# delta.net
KiCad netlist of a schematic drawn in EasyEDA Pro
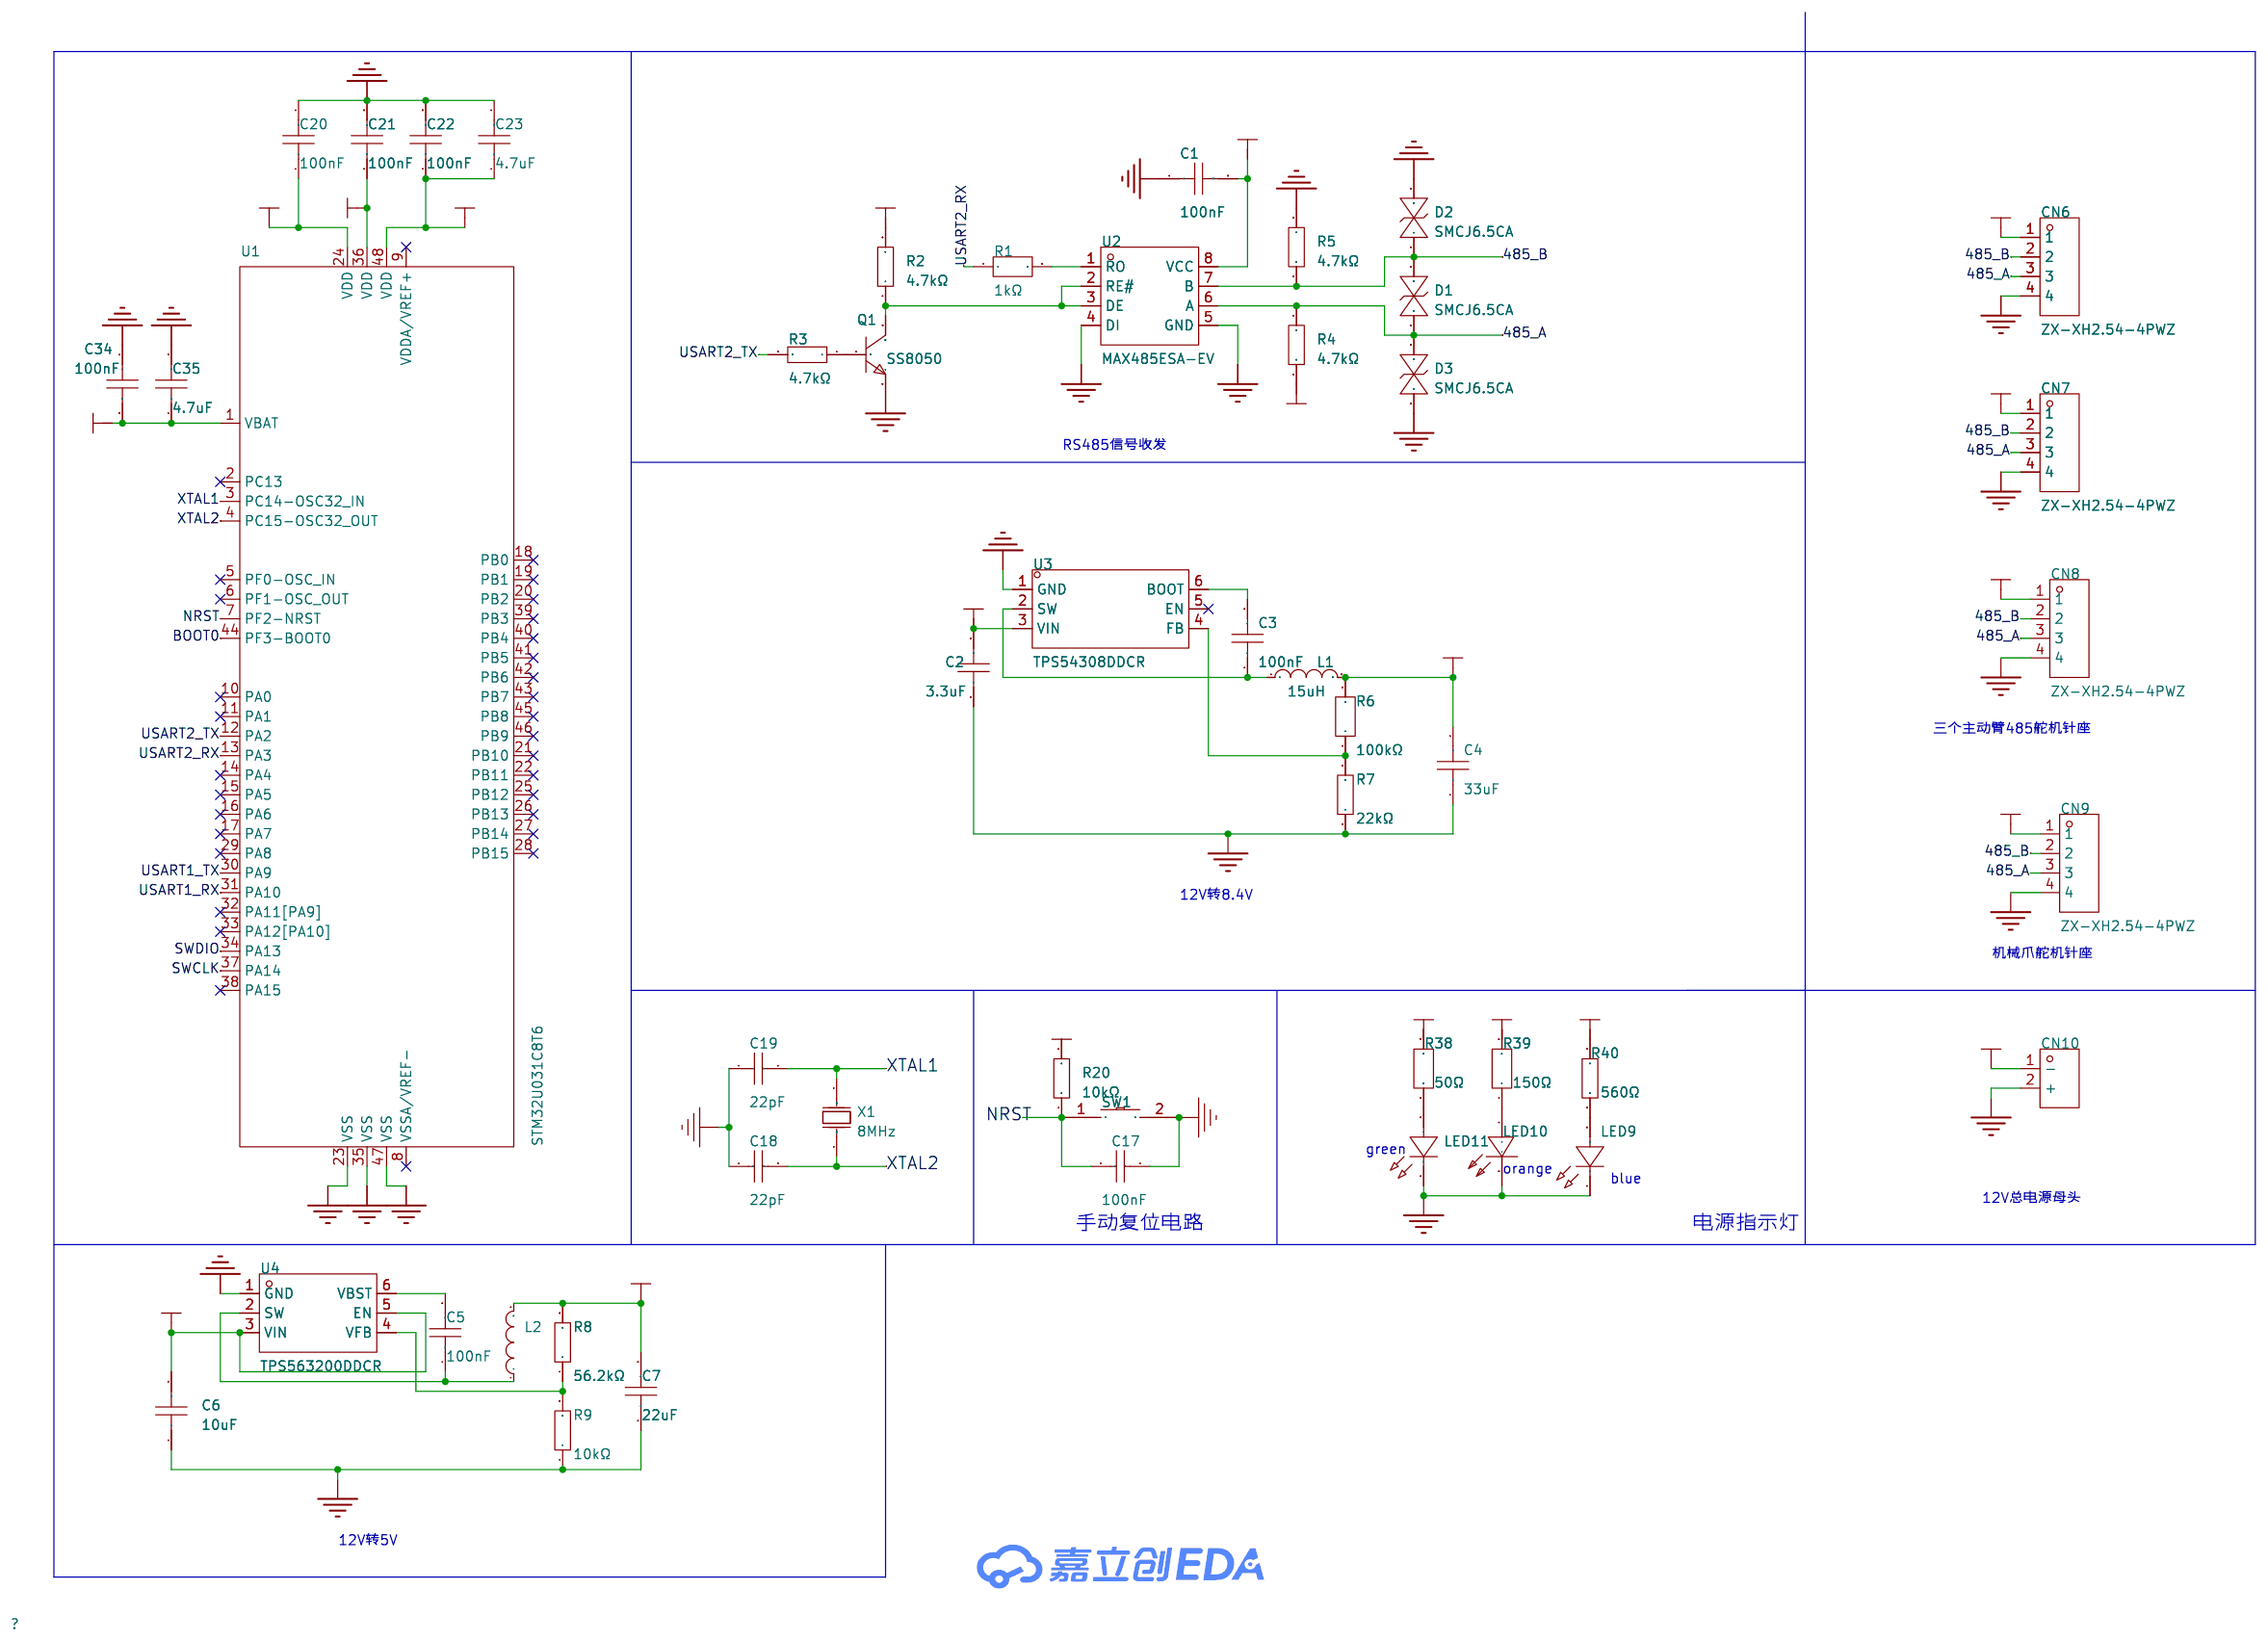
[diagram p0: P1]
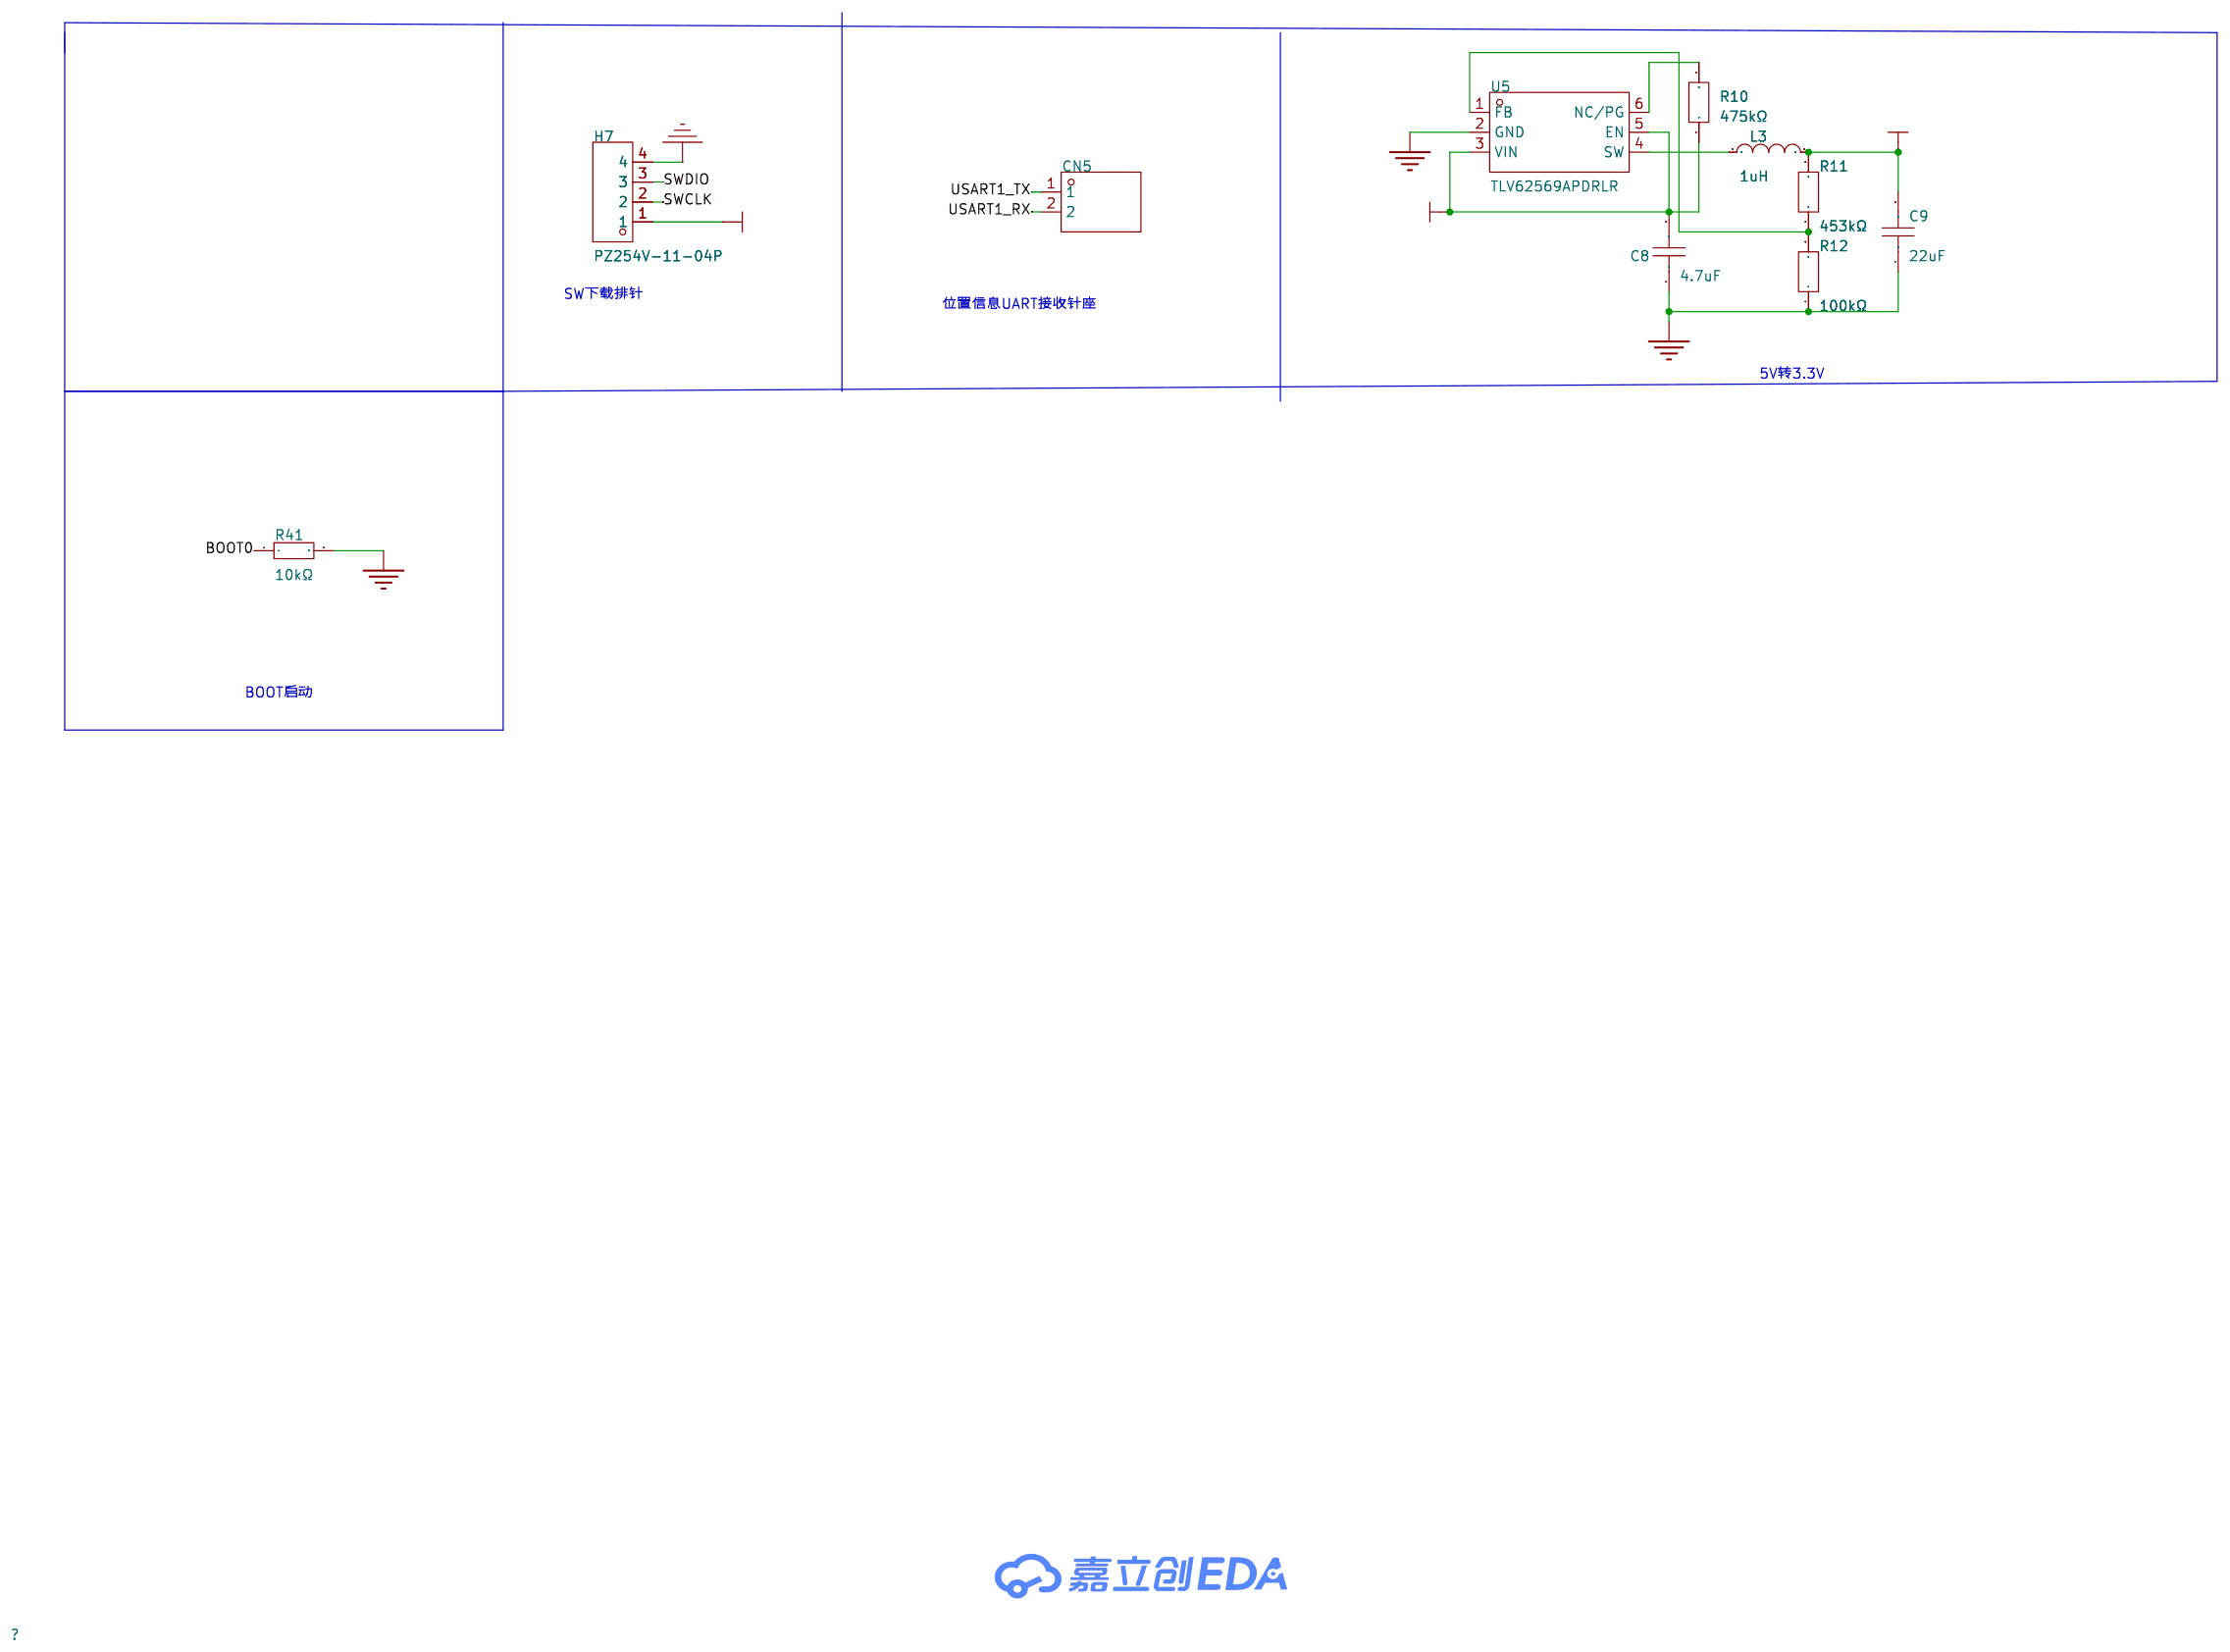
[diagram p1: P2]

(export (version "E")
  (design (tool "Eeschema 10.0.6"))
  (components
    (comp (ref "C1")
      (value "100nF")
      (footprint "easyedapro:C0603")
      (description "容值:100nF;精度:±10%;额定电压:50V;温度系数:X7R;")
      (fields
        (field (name "Manufacturer Part") "CGA0603X7R104K500JT")
        (field (name "Manufacturer") "HRE(芯声)")
      )
      (libsource (lib "easyedapro") (part "CGA0603X7R104K500JT"))
    )
    (comp (ref "C2")
      (value "3.3uF")
      (footprint "easyedapro:C0603")
      (description "容值:3.3uF;精度:±10%;额定电压:35V;温度系数:X5R;")
      (fields (field (name "Manufacturer Part") "C1608X5R1V335K080AC") (field (name "Manufacturer") "TDK"))
      (libsource (lib "easyedapro") (part "C1608X5R1V335K080AC"))
    )
    (comp (ref "C3")
      (value "100nF")
      (footprint "easyedapro:C0805")
      (description "容值:100nF;精度:±20%;额定电压:50V;材质(温度系数):X7R;")
      (fields (field (name "Manufacturer Part") "C0805C104M5RACTU") (field (name "Manufacturer") "KEMET(基美)"))
      (libsource (lib "easyedapro") (part "C0805C104M5RACTU"))
    )
    (comp (ref "C4")
      (value "33uF")
      (footprint "easyedapro:C0805")
      (description "容值:33uF;精度:±20%;额定电压:10V;温度系数:X5R;")
      (fields (field (name "Manufacturer Part") "C2012X5R1A336M125AC") (field (name "Manufacturer") "TDK"))
      (libsource (lib "easyedapro") (part "C2012X5R1A336M125AC"))
    )
    (comp (ref "C5")
      (value "100nF")
      (footprint "easyedapro:C0805")
      (description "容值:100nF;精度:±10%;额定电压:25V;材质(温度系数):X7R;")
      (fields (field (name "Manufacturer Part") "08053C104KAT2A") (field (name "Manufacturer") "Kyocera AVX"))
      (libsource (lib "easyedapro") (part "08053C104KAT2A"))
    )
    (comp (ref "C6")
      (value "10uF")
      (footprint "easyedapro:C0805")
      (description "容值:10uF;精度:±10%;额定电压:25V;材质(温度系数):X5R;")
      (fields
        (field (name "Manufacturer Part") "CL21A106KAYNNNE")
        (field (name "Manufacturer") "SAMSUNG(三星)")
      )
      (libsource (lib "easyedapro") (part "CL21A106KAYNNNE"))
    )
    (comp (ref "C7")
      (value "22uF")
      (footprint "easyedapro:C0805")
      (description "容值:22uF;精度:±20%;额定电压:10V;材质(温度系数):X5R;")
      (fields
        (field (name "Manufacturer Part") "GRM21BR61A226ME44L")
        (field (name "Manufacturer") "muRata(村田)")
      )
      (libsource (lib "easyedapro") (part "GRM21BR61A226ME44L"))
    )
    (comp (ref "C17")
      (value "100nF")
      (footprint "easyedapro:C0805")
      (description "容值:100nF;精度:±10%;额定电压:100V;材质(温度系数):X7R;")
      (fields
        (field (name "Manufacturer Part") "CL21B104KCFNNNE")
        (field (name "Manufacturer") "SAMSUNG(三星)")
      )
      (libsource (lib "easyedapro") (part "CL21B104KCFNNNE"))
    )
    (comp (ref "C18")
      (value "22pF")
      (footprint "easyedapro:C0805")
      (description "容值:22pF;精度:±5%;额定电压:50V;材质(温度系数):C0G;")
      (fields
        (field (name "Manufacturer Part") "CL21C220JBANNNC")
        (field (name "Manufacturer") "SAMSUNG(三星)")
      )
      (libsource (lib "easyedapro") (part "CL21C220JBANNNC"))
    )
    (comp (ref "C19")
      (value "22pF")
      (footprint "easyedapro:C0805")
      (description "容值:22pF;精度:±5%;额定电压:50V;材质(温度系数):C0G;")
      (fields
        (field (name "Manufacturer Part") "CL21C220JBANNNC")
        (field (name "Manufacturer") "SAMSUNG(三星)")
      )
      (libsource (lib "easyedapro") (part "CL21C220JBANNNC"))
    )
    (comp (ref "C20")
      (value "100nF")
      (footprint "easyedapro:C0805")
      (description "容值:100nF;精度:±10%;额定电压:50V;材质(温度系数):X7R;")
      (fields
        (field (name "Manufacturer Part") "CC0805KRX7R9BB104")
        (field (name "Manufacturer") "YAGEO(国巨)")
      )
      (libsource (lib "easyedapro") (part "CC0805KRX7R9BB104"))
    )
    (comp (ref "C21")
      (value "100nF")
      (footprint "easyedapro:C0805")
      (description "容值:100nF;精度:±10%;额定电压:50V;材质(温度系数):X7R;")
      (fields
        (field (name "Manufacturer Part") "CC0805KRX7R9BB104")
        (field (name "Manufacturer") "YAGEO(国巨)")
      )
      (libsource (lib "easyedapro") (part "CC0805KRX7R9BB104"))
    )
    (comp (ref "C22")
      (value "100nF")
      (footprint "easyedapro:C0805")
      (description "容值:100nF;精度:±10%;额定电压:50V;材质(温度系数):X7R;")
      (fields
        (field (name "Manufacturer Part") "CC0805KRX7R9BB104")
        (field (name "Manufacturer") "YAGEO(国巨)")
      )
      (libsource (lib "easyedapro") (part "CC0805KRX7R9BB104"))
    )
    (comp (ref "C23")
      (value "4.7uF")
      (footprint "easyedapro:C0805")
      (description "容值:4.7uF;精度:±10%;额定电压:35V;材质(温度系数):X7R;")
      (fields
        (field (name "Manufacturer Part") "CGA0805X7R475K350MT")
        (field (name "Manufacturer") "HRE(芯声)")
      )
      (libsource (lib "easyedapro") (part "CGA0805X7R475K350MT"))
    )
    (comp (ref "C34")
      (value "100nF")
      (footprint "easyedapro:C0805")
      (description "容值:100nF;精度:±10%;额定电压:50V;材质(温度系数):X7R;")
      (fields
        (field (name "Manufacturer Part") "CC0805KRX7R9BB104")
        (field (name "Manufacturer") "YAGEO(国巨)")
      )
      (libsource (lib "easyedapro") (part "CC0805KRX7R9BB104"))
    )
    (comp (ref "C35")
      (value "4.7uF")
      (footprint "easyedapro:C0805")
      (description "容值:4.7uF;精度:±10%;额定电压:35V;材质(温度系数):X7R;")
      (fields
        (field (name "Manufacturer Part") "CGA0805X7R475K350MT")
        (field (name "Manufacturer") "HRE(芯声)")
      )
      (libsource (lib "easyedapro") (part "CGA0805X7R475K350MT"))
    )
    (comp (ref "CN6")
      (value "ZX-XH2.54-4PWZ")
      (footprint "easyedapro:CONN-TH_4P-P2.50_ZX-XH2.54-4PWZ")
      (fields (field (name "Manufacturer") "Megastar(兆星)"))
      (libsource (lib "easyedapro") (part "ZX-XH2.54-4PWZ"))
    )
    (comp (ref "CN7")
      (value "ZX-XH2.54-4PWZ")
      (footprint "easyedapro:CONN-TH_4P-P2.50_ZX-XH2.54-4PWZ")
      (fields (field (name "Manufacturer") "Megastar(兆星)"))
      (libsource (lib "easyedapro") (part "ZX-XH2.54-4PWZ"))
    )
    (comp (ref "CN8")
      (value "ZX-XH2.54-4PWZ")
      (footprint "easyedapro:CONN-TH_4P-P2.50_ZX-XH2.54-4PWZ")
      (fields (field (name "Manufacturer") "Megastar(兆星)"))
      (libsource (lib "easyedapro") (part "ZX-XH2.54-4PWZ"))
    )
    (comp (ref "CN9")
      (value "ZX-XH2.54-4PWZ")
      (footprint "easyedapro:CONN-TH_4P-P2.50_ZX-XH2.54-4PWZ")
      (fields (field (name "Manufacturer") "Megastar(兆星)"))
      (libsource (lib "easyedapro") (part "ZX-XH2.54-4PWZ"))
    )
    (comp (ref "CN10")
      (value "XT30UPB-M")
      (footprint "easyedapro:CONN-TH_XT30UPB-M")
      (description "类别:-;类型1:-;")
      (fields (field (name "Manufacturer") "AMASS(艾迈斯)"))
      (libsource (lib "easyedapro") (part "XT30UPB-M"))
    )
    (comp (ref "D1")
      (value "SMCJ6.5CA")
      (footprint "easyedapro:SMC_L6.8-W5.9-LS7.9-BI")
      (fields (field (name "Manufacturer") "Brightking(君耀电子)"))
      (libsource (lib "easyedapro") (part "SMCJ6.5CA_C20623833"))
    )
    (comp (ref "D2")
      (value "SMCJ6.5CA")
      (footprint "easyedapro:SMC_L6.8-W5.9-LS7.9-BI")
      (fields (field (name "Manufacturer") "Brightking(君耀电子)"))
      (libsource (lib "easyedapro") (part "SMCJ6.5CA_C20623833"))
    )
    (comp (ref "D3")
      (value "SMCJ6.5CA")
      (footprint "easyedapro:SMC_L6.8-W5.9-LS7.9-BI")
      (fields (field (name "Manufacturer") "Brightking(君耀电子)"))
      (libsource (lib "easyedapro") (part "SMCJ6.5CA_C20623833"))
    )
    (comp (ref "L1")
      (value "15uH")
      (footprint "easyedapro:IND-SMD_L10.2-W10.0")
      (description "电感值:15uH;精度:±20%;")
      (fields
        (field (name "Manufacturer Part") "MSS1038-153MLC")
        (field (name "Manufacturer") "Coilcraft(线艺)")
      )
      (libsource (lib "easyedapro") (part "MSS1038-153MLC"))
    )
    (comp (ref "L2")
      (value "VLP8040T-3R3N")
      (footprint "easyedapro:IND-SMD_L8.7-W8.6")
      (description "精度:±30%;")
      (fields (field (name "Manufacturer") "TDK"))
      (libsource (lib "easyedapro") (part "VLP8040T-3R3N"))
    )
    (comp (ref "LED9")
      (value "XL-1608UBC-04")
      (footprint "easyedapro:LED0603-RD_BLUE")
      (fields (field (name "Manufacturer") "XINGLIGHT(成兴光)"))
      (libsource (lib "easyedapro") (part "XL-1608UBC-04"))
    )
    (comp (ref "LED10")
      (value "SZYY0603O")
      (footprint "easyedapro:LED0603-R-RD_ORANGE")
      (fields (field (name "Manufacturer") "yongyu(永裕光电)"))
      (libsource (lib "easyedapro") (part "SZYY0603O"))
    )
    (comp (ref "LED11")
      (value "TZ-P2-0603YGTCS1-0.6T")
      (footprint "easyedapro:LED0603-RD")
      (fields (field (name "Manufacturer") "TUOZHAN(拓展光电)"))
      (libsource (lib "easyedapro") (part "TZ-P2-0603YGTCS1-0.6T"))
    )
    (comp (ref "Q1")
      (value "SS8050")
      (footprint "easyedapro:SOT-23-3_L2.9-W1.3-P1.90-LS2.4-BR")
      (fields (field (name "Manufacturer") "Doeshare(德芯)"))
      (libsource (lib "easyedapro") (part "SS8050_C2931717"))
    )
    (comp (ref "R1")
      (value "1kΩ")
      (footprint "easyedapro:R0603")
      (description "电阻类型:厚膜电阻;阻值:1kΩ;精度:±1%;功率:100mW;最大工作电压:75V;")
      (fields (field (name "Manufacturer Part") "FCR0603F1K") (field (name "Manufacturer") "VO(翔胜)"))
      (libsource (lib "easyedapro") (part "FCR0603F1K"))
    )
    (comp (ref "R2")
      (value "4.7kΩ")
      (footprint "easyedapro:R0603")
      (description "电阻类型:厚膜电阻;阻值:4.7kΩ;精度:±1%;功率:100mW;最大工作电压:75V;温度系数:±100ppm/°C;")
      (fields
        (field (name "Manufacturer Part") "0603WAF4701T5E")
        (field (name "Manufacturer") "UNI-ROYAL(厚声)")
      )
      (libsource (lib "easyedapro") (part "0603WAF4701T5E"))
    )
    (comp (ref "R3")
      (value "4.7kΩ")
      (footprint "easyedapro:R0603")
      (description "电阻类型:厚膜电阻;阻值:4.7kΩ;精度:±1%;功率:100mW;最大工作电压:75V;温度系数:±100ppm/°C;")
      (fields
        (field (name "Manufacturer Part") "0603WAF4701T5E")
        (field (name "Manufacturer") "UNI-ROYAL(厚声)")
      )
      (libsource (lib "easyedapro") (part "0603WAF4701T5E"))
    )
    (comp (ref "R4")
      (value "4.7kΩ")
      (footprint "easyedapro:R0603")
      (description "电阻类型:厚膜电阻;阻值:4.7kΩ;精度:±1%;功率:100mW;最大工作电压:75V;温度系数:±100ppm/°C;")
      (fields
        (field (name "Manufacturer Part") "0603WAF4701T5E")
        (field (name "Manufacturer") "UNI-ROYAL(厚声)")
      )
      (libsource (lib "easyedapro") (part "0603WAF4701T5E"))
    )
    (comp (ref "R5")
      (value "4.7kΩ")
      (footprint "easyedapro:R0603")
      (description "电阻类型:厚膜电阻;阻值:4.7kΩ;精度:±1%;功率:100mW;最大工作电压:75V;温度系数:±100ppm/°C;")
      (fields
        (field (name "Manufacturer Part") "0603WAF4701T5E")
        (field (name "Manufacturer") "UNI-ROYAL(厚声)")
      )
      (libsource (lib "easyedapro") (part "0603WAF4701T5E"))
    )
    (comp (ref "R6")
      (value "100kΩ")
      (footprint "easyedapro:R0402")
      (description "电阻类型:厚膜电阻;阻值:100kΩ;精度:±1%;功率:63mW;工作电压:75V;温度系数:±100ppm/°C;")
      (fields
        (field (name "Manufacturer Part") "CRCW0402100KFKED")
        (field (name "Manufacturer") "VISHAY(威世)")
      )
      (libsource (lib "easyedapro") (part "CRCW0402100KFKED"))
    )
    (comp (ref "R7")
      (value "22kΩ")
      (footprint "easyedapro:R0603")
      (description "电阻类型:厚膜电阻;阻值:22kΩ;精度:±1%;功率:100mW;工作电压:75V;温度系数:±100ppm/°C;")
      (fields (field (name "Manufacturer Part") "RC0603FR-0722KL") (field (name "Manufacturer") "YAGEO(国巨)"))
      (libsource (lib "easyedapro") (part "RC0603FR-0722KL"))
    )
    (comp (ref "R8")
      (value "56.2kΩ")
      (footprint "easyedapro:R0201")
      (description "电阻类型:厚膜电阻;阻值:56.2kΩ;精度:±1%;功率:50mW;工作电压:25V;温度系数:±200ppm/°C;")
      (fields (field (name "Manufacturer Part") "RC0201FR-0756K2L") (field (name "Manufacturer") "YAGEO(国巨)"))
      (libsource (lib "easyedapro") (part "RC0201FR-0756K2L"))
    )
    (comp (ref "R9")
      (value "10kΩ")
      (footprint "easyedapro:R0201")
      (description "电阻类型:厚膜电阻;阻值:10kΩ;精度:±1%;功率:50mW;工作电压:25V;温度系数:±200ppm/°C;")
      (fields (field (name "Manufacturer Part") "RC0201FR-0710KL") (field (name "Manufacturer") "YAGEO(国巨)"))
      (libsource (lib "easyedapro") (part "RC0201FR-0710KL"))
    )
    (comp (ref "R20")
      (value "10kΩ")
      (footprint "easyedapro:R0805")
      (description "电阻类型:厚膜电阻;阻值:10kΩ;精度:±1%;功率:125mW;最大工作电压:150V;温度系数:±100ppm/°C;")
      (fields
        (field (name "Manufacturer Part") "0805W8F1002T5E")
        (field (name "Manufacturer") "UNI-ROYAL(厚声)")
      )
      (libsource (lib "easyedapro") (part "0805W8F1002T5E"))
    )
    (comp (ref "R38")
      (value "50Ω")
      (footprint "easyedapro:R0805")
      (description "电阻类型:薄膜电阻;阻值:50Ω;精度:±1%;功率:125mW;最大工作电压:150V;温度系数:±25ppm/°C;")
      (fields (field (name "Manufacturer Part") "ARG05FTC0500") (field (name "Manufacturer") "Viking(光颉)"))
      (libsource (lib "easyedapro") (part "ARG05FTC0500"))
    )
    (comp (ref "R39")
      (value "150Ω")
      (footprint "easyedapro:R0805")
      (description "电阻类型:厚膜电阻;阻值:150Ω;精度:±5%;功率:125mW;最大工作电压:150V;温度系数:±100ppm/°C;")
      (fields (field (name "Manufacturer Part") "FRC0805J151 TS") (field (name "Manufacturer") "FOJAN(富捷)"))
      (libsource (lib "easyedapro") (part "FRC0805J151 TS"))
    )
    (comp (ref "R40")
      (value "560Ω")
      (footprint "easyedapro:R0805")
      (description "电阻类型:厚膜电阻;阻值:560Ω;精度:±1%;功率:125mW;最大工作电压:150V;温度系数:±100ppm/°C;")
      (fields
        (field (name "Manufacturer Part") "0805W8F5600T5E")
        (field (name "Manufacturer") "UNI-ROYAL(厚声)")
      )
      (libsource (lib "easyedapro") (part "0805W8F5600T5E"))
    )
    (comp (ref "SW1")
      (value "TS-1101-C-W")
      (footprint "easyedapro:SW-SMD_L6.0-W3.3-LS8.0")
      (fields (field (name "Manufacturer") "XKB Connectivity(中国星坤)"))
      (libsource (lib "easyedapro") (part "TS-1101-C-W"))
    )
    (comp (ref "U1")
      (value "STM32U031C8T6")
      (footprint "easyedapro:LQFP-48_L7.0-W7.0-P0.50-LS9.0-BL_1")
      (libsource (lib "easyedapro") (part "STM32U031C8T6"))
    )
    (comp (ref "U2")
      (value "MAX485ESA-EV")
      (footprint "easyedapro:SOIC-8_L4.9-W3.9-P1.27-LS6.0-BL")
      (description "低功耗、限摆率、RS-485/RS-422收发器")
      (fields (field (name "Manufacturer") "EVVO(翊欧)"))
      (libsource (lib "easyedapro") (part "MAX485ESA-EV"))
    )
    (comp (ref "U3")
      (value "TPS54308DDCR")
      (footprint "easyedapro:SOT-23-6_L2.9-W1.6-P0.95-LS2.8-BR")
      (description "功能类型:降压型;输出类型:固定;工作电压:4.5V~28V;输出电压:3.3V;输出电流:3A;")
      (fields (field (name "Manufacturer") "TI(德州仪器)"))
      (libsource (lib "easyedapro") (part "TPS54308DDCR"))
    )
    (comp (ref "U4")
      (value "TPS563200DDCR")
      (footprint "easyedapro:SOT-23-6_L2.9-W1.6-P0.95-LS2.8-BR")
      (description "功能类型:降压型;输出类型:可调;工作电压:4.5V~17V;输出电压:760mV~7V;输出电流:3A;")
      (fields (field (name "Manufacturer") "TI(德州仪器)"))
      (libsource (lib "easyedapro") (part "TPS563200DDCR"))
    )
    (comp (ref "X1")
      (value "8MHz")
      (footprint "easyedapro:CRYSTAL-SMD_L11.5-W4.8-LS12.7")
      (description "晶振类型:贴片晶振;频率:8MHz;常温频差:±20ppm;负载电容:20pF;频率稳定度:±30ppm;")
      (fields (field (name "Manufacturer Part") "X49SM8MSD2SC") (field (name "Manufacturer") "YXC(扬兴晶振)"))
      (libsource (lib "easyedapro") (part "X49SM8MSD2SC"))
    )
    (comp (ref "C8")
      (value "4.7uF")
      (footprint "easyedapro:C0603")
      (description "容值:4.7uF;精度:±10%;额定电压:16V;温度系数:X5R;")
      (fields
        (field (name "Manufacturer Part") "CL10A475KO8NNNC")
        (field (name "Manufacturer") "SAMSUNG(三星)")
      )
      (libsource (lib "easyedapro") (part "CL10A475KO8NNNC"))
    )
    (comp (ref "C9")
      (value "22uF")
      (footprint "easyedapro:C0603")
      (description "容值:22uF;精度:±20%;额定电压:6.3V;材质(温度系数):X5R;")
      (fields
        (field (name "Manufacturer Part") "GRM188R60J226MEA0D")
        (field (name "Manufacturer") "muRata(村田)")
      )
      (libsource (lib "easyedapro") (part "GRM188R60J226MEA0D"))
    )
    (comp (ref "CN5")
      (value "B2B-XH-A(LF)(SN)")
      (footprint "easyedapro:CONN-TH_B2B-XH-A-LF-SN")
      (fields (field (name "Manufacturer") "JST"))
      (libsource (lib "easyedapro") (part "B2B-XH-A (LF)(SN)"))
    )
    (comp (ref "H7")
      (value "PZ254V-11-04P")
      (footprint "easyedapro:HDR-TH_4P-P2.54-V-M")
      (fields (field (name "Manufacturer") "XFCN(兴飞)"))
      (libsource (lib "easyedapro") (part "PZ254V-11-04P_C2691448"))
    )
    (comp (ref "L3")
      (value "1uH")
      (footprint "easyedapro:IND-SMD_L8.2-W7.9")
      (description "电感值:1uH;精度:±30%;额定电流:7.8A;饱和电流(Isat):11A;类型:-;")
      (fields (field (name "Manufacturer Part") "SRN8040-1R0Y") (field (name "Manufacturer") "BOURNS"))
      (libsource (lib "easyedapro") (part "SRN8040-1R0Y"))
    )
    (comp (ref "R10")
      (value "475kΩ")
      (footprint "easyedapro:R0402")
      (description "电阻类型:厚膜电阻;阻值:475kΩ;精度:±1%;功率:62.5mW;最大工作电压:75V;温度系数:±100ppm/°C;")
      (fields
        (field (name "Manufacturer Part") "CRCW0402475KFKED")
        (field (name "Manufacturer") "VISHAY(威世)")
      )
      (libsource (lib "easyedapro") (part "CRCW0402475KFKED"))
    )
    (comp (ref "R11")
      (value "453kΩ")
      (footprint "easyedapro:R0402")
      (description "电阻类型:厚膜电阻;阻值:453kΩ;精度:±1%;功率:62.5mW;工作电压:50V;温度系数:±100ppm/°C;")
      (fields
        (field (name "Manufacturer Part") "CRCW0402453KFKED")
        (field (name "Manufacturer") "VISHAY(威世)")
      )
      (libsource (lib "easyedapro") (part "CRCW0402453KFKED"))
    )
    (comp (ref "R12")
      (value "100kΩ")
      (footprint "easyedapro:R0402")
      (description "电阻类型:厚膜电阻;阻值:100kΩ;精度:±1%;功率:63mW;工作电压:75V;温度系数:±100ppm/°C;")
      (fields
        (field (name "Manufacturer Part") "CRCW0402100KFKED")
        (field (name "Manufacturer") "VISHAY(威世)")
      )
      (libsource (lib "easyedapro") (part "CRCW0402100KFKED"))
    )
    (comp (ref "R41")
      (value "10kΩ")
      (footprint "easyedapro:R0805")
      (description "电阻类型:厚膜电阻;阻值:10kΩ;精度:±1%;功率:125mW;最大工作电压:150V;温度系数:±100ppm/°C;")
      (fields
        (field (name "Manufacturer Part") "0805W8F1002T5E")
        (field (name "Manufacturer") "UNI-ROYAL(厚声)")
      )
      (libsource (lib "easyedapro") (part "0805W8F1002T5E"))
    )
    (comp (ref "U5")
      (value "TLV62569APDRLR")
      (footprint "easyedapro:SOT-563_L1.6-W1.2-P0.50-LS1.6-BR")
      (description "功能类型:降压型;输出类型:可调;工作电压:2.5V~5.5V;输出电压:600mV~5.5V;输出电流:2A;")
      (fields (field (name "Manufacturer") "TI(德州仪器)"))
      (libsource (lib "easyedapro") (part "TLV62569APDRLR"))
    )
  )
  (nets
    (net (code "1") (name "3.3V") (class "Default")
      (node (ref "C1") (pin "2") (pinfunction "2_2") (pintype "unspecified"))
      (node (ref "C20") (pin "1") (pinfunction "1_1") (pintype "unspecified"))
      (node (ref "C21") (pin "1") (pinfunction "1_1") (pintype "unspecified"))
      (node (ref "C22") (pin "1") (pinfunction "1_1") (pintype "unspecified"))
      (node (ref "C23") (pin "1") (pinfunction "1_1") (pintype "unspecified"))
      (node (ref "C34") (pin "2") (pinfunction "2_2") (pintype "unspecified"))
      (node (ref "C35") (pin "1") (pinfunction "1_1") (pintype "unspecified"))
      (node (ref "C9") (pin "2") (pinfunction "2_2") (pintype "unspecified"))
      (node (ref "H7") (pin "1") (pinfunction "1_1") (pintype "unspecified"))
      (node (ref "L3") (pin "2") (pinfunction "2_2") (pintype "unspecified"))
      (node (ref "R11") (pin "2") (pinfunction "2_2") (pintype "unspecified"))
      (node (ref "R2") (pin "2") (pinfunction "2_2") (pintype "input"))
      (node (ref "R20") (pin "2") (pinfunction "2_2") (pintype "input"))
      (node (ref "R38") (pin "2") (pinfunction "2_2") (pintype "unspecified"))
      (node (ref "R4") (pin "2") (pinfunction "2_2") (pintype "input"))
      (node (ref "U1") (pin "1") (pinfunction "VBAT_1") (pintype "unspecified"))
      (node (ref "U1") (pin "24") (pinfunction "VDD_24") (pintype "unspecified"))
      (node (ref "U1") (pin "36") (pinfunction "VDD_36") (pintype "unspecified"))
      (node (ref "U1") (pin "48") (pinfunction "VDD_48") (pintype "unspecified"))
      (node (ref "U2") (pin "8") (pinfunction "VCC_8") (pintype "unspecified"))
    )
    (net (code "2") (name "5V") (class "Default")
      (node (ref "C7") (pin "2") (pinfunction "2_2") (pintype "unspecified"))
      (node (ref "C8") (pin "2") (pinfunction "2_2") (pintype "unspecified"))
      (node (ref "L2") (pin "2") (pinfunction "2_2") (pintype "unspecified"))
      (node (ref "R10") (pin "1") (pinfunction "1_1") (pintype "unspecified"))
      (node (ref "R39") (pin "2") (pinfunction "2_2") (pintype "unspecified"))
      (node (ref "R8") (pin "2") (pinfunction "2_2") (pintype "unspecified"))
      (node (ref "U5") (pin "3") (pinfunction "VIN_3") (pintype "unspecified"))
      (node (ref "U5") (pin "5") (pinfunction "EN_5") (pintype "unspecified"))
    )
    (net (code "3") (name "8.4V") (class "Default")
      (node (ref "C4") (pin "2") (pinfunction "2_2") (pintype "unspecified"))
      (node (ref "CN6") (pin "1") (pinfunction "1_1") (pintype "unspecified"))
      (node (ref "CN7") (pin "1") (pinfunction "1_1") (pintype "unspecified"))
      (node (ref "CN8") (pin "1") (pinfunction "1_1") (pintype "unspecified"))
      (node (ref "CN9") (pin "1") (pinfunction "1_1") (pintype "unspecified"))
      (node (ref "L1") (pin "2") (pinfunction "2_2") (pintype "unspecified"))
      (node (ref "R6") (pin "2") (pinfunction "2_2") (pintype "unspecified"))
    )
    (net (code "4") (name "12V") (class "Default")
      (node (ref "C2") (pin "2") (pinfunction "2_2") (pintype "unspecified"))
      (node (ref "C6") (pin "2") (pinfunction "2_2") (pintype "unspecified"))
      (node (ref "CN10") (pin "1") (pinfunction "-_1") (pintype "unspecified"))
      (node (ref "R40") (pin "2") (pinfunction "2_2") (pintype "input"))
      (node (ref "U3") (pin "3") (pinfunction "VIN_3") (pintype "unspecified"))
      (node (ref "U4") (pin "3") (pinfunction "VIN_3") (pintype "unspecified"))
      (node (ref "U4") (pin "5") (pinfunction "EN_5") (pintype "unspecified"))
    )
    (net (code "5") (name "485_A") (class "Default")
      (node (ref "CN6") (pin "3") (pinfunction "3_3") (pintype "unspecified"))
      (node (ref "CN7") (pin "3") (pinfunction "3_3") (pintype "unspecified"))
      (node (ref "CN8") (pin "3") (pinfunction "3_3") (pintype "unspecified"))
      (node (ref "CN9") (pin "3") (pinfunction "3_3") (pintype "unspecified"))
      (node (ref "D1") (pin "1") (pinfunction "1_1") (pintype "unspecified"))
      (node (ref "D3") (pin "2") (pinfunction "2_2") (pintype "unspecified"))
      (node (ref "R4") (pin "1") (pinfunction "1_1") (pintype "input"))
      (node (ref "U2") (pin "6") (pinfunction "A_6") (pintype "unspecified"))
    )
    (net (code "6") (name "485_B") (class "Default")
      (node (ref "CN6") (pin "2") (pinfunction "2_2") (pintype "unspecified"))
      (node (ref "CN7") (pin "2") (pinfunction "2_2") (pintype "unspecified"))
      (node (ref "CN8") (pin "2") (pinfunction "2_2") (pintype "unspecified"))
      (node (ref "CN9") (pin "2") (pinfunction "2_2") (pintype "unspecified"))
      (node (ref "D1") (pin "2") (pinfunction "2_2") (pintype "unspecified"))
      (node (ref "D2") (pin "1") (pinfunction "1_1") (pintype "unspecified"))
      (node (ref "R5") (pin "2") (pinfunction "2_2") (pintype "input"))
      (node (ref "U2") (pin "7") (pinfunction "B_7") (pintype "unspecified"))
    )
    (net (code "7") (name "BOOT0") (class "Default")
      (node (ref "R41") (pin "1") (pinfunction "1_1") (pintype "input"))
      (node (ref "U1") (pin "44") (pinfunction "PF3-BOOT0_44") (pintype "unspecified"))
    )
    (net (code "8") (name "GND") (class "Default")
      (node (ref "C1") (pin "1") (pinfunction "1_1") (pintype "unspecified"))
      (node (ref "C17") (pin "2") (pinfunction "2_2") (pintype "input"))
      (node (ref "C18") (pin "1") (pinfunction "1_1") (pintype "input"))
      (node (ref "C19") (pin "1") (pinfunction "1_1") (pintype "input"))
      (node (ref "C2") (pin "1") (pinfunction "1_1") (pintype "unspecified"))
      (node (ref "C20") (pin "2") (pinfunction "2_2") (pintype "unspecified"))
      (node (ref "C21") (pin "2") (pinfunction "2_2") (pintype "unspecified"))
      (node (ref "C22") (pin "2") (pinfunction "2_2") (pintype "unspecified"))
      (node (ref "C23") (pin "2") (pinfunction "2_2") (pintype "unspecified"))
      (node (ref "C34") (pin "1") (pinfunction "1_1") (pintype "unspecified"))
      (node (ref "C35") (pin "2") (pinfunction "2_2") (pintype "unspecified"))
      (node (ref "C4") (pin "1") (pinfunction "1_1") (pintype "unspecified"))
      (node (ref "C6") (pin "1") (pinfunction "1_1") (pintype "unspecified"))
      (node (ref "C7") (pin "1") (pinfunction "1_1") (pintype "unspecified"))
      (node (ref "C8") (pin "1") (pinfunction "1_1") (pintype "unspecified"))
      (node (ref "C9") (pin "1") (pinfunction "1_1") (pintype "unspecified"))
      (node (ref "CN10") (pin "2") (pinfunction "+_2") (pintype "unspecified"))
      (node (ref "CN6") (pin "4") (pinfunction "4_4") (pintype "unspecified"))
      (node (ref "CN7") (pin "4") (pinfunction "4_4") (pintype "unspecified"))
      (node (ref "CN8") (pin "4") (pinfunction "4_4") (pintype "unspecified"))
      (node (ref "CN9") (pin "4") (pinfunction "4_4") (pintype "unspecified"))
      (node (ref "D2") (pin "2") (pinfunction "2_2") (pintype "unspecified"))
      (node (ref "D3") (pin "1") (pinfunction "1_1") (pintype "unspecified"))
      (node (ref "H7") (pin "4") (pinfunction "4_4") (pintype "unspecified"))
      (node (ref "LED10") (pin "2") (pinfunction "-_2") (pintype "unspecified"))
      (node (ref "LED11") (pin "1") (pinfunction "K_1") (pintype "unspecified"))
      (node (ref "LED9") (pin "1") (pinfunction "K_1") (pintype "unspecified"))
      (node (ref "Q1") (pin "2") (pinfunction "E_2") (pintype "unspecified"))
      (node (ref "R12") (pin "1") (pinfunction "1_1") (pintype "unspecified"))
      (node (ref "R41") (pin "2") (pinfunction "2_2") (pintype "input"))
      (node (ref "R5") (pin "1") (pinfunction "1_1") (pintype "input"))
      (node (ref "R7") (pin "1") (pinfunction "1_1") (pintype "input"))
      (node (ref "R9") (pin "1") (pinfunction "1_1") (pintype "unspecified"))
      (node (ref "SW1") (pin "2") (pinfunction "2_2") (pintype "unspecified"))
      (node (ref "U1") (pin "23") (pinfunction "VSS_23") (pintype "unspecified"))
      (node (ref "U1") (pin "35") (pinfunction "VSS_35") (pintype "unspecified"))
      (node (ref "U1") (pin "47") (pinfunction "VSS_47") (pintype "unspecified"))
      (node (ref "U2") (pin "4") (pinfunction "DI_4") (pintype "unspecified"))
      (node (ref "U2") (pin "5") (pinfunction "GND_5") (pintype "unspecified"))
      (node (ref "U3") (pin "1") (pinfunction "GND_1") (pintype "unspecified"))
      (node (ref "U4") (pin "1") (pinfunction "GND_1") (pintype "unspecified"))
      (node (ref "U5") (pin "2") (pinfunction "GND_2") (pintype "unspecified"))
    )
    (net (code "9") (name "NRST") (class "Default")
      (node (ref "C17") (pin "1") (pinfunction "1_1") (pintype "input"))
      (node (ref "R20") (pin "1") (pinfunction "1_1") (pintype "input"))
      (node (ref "SW1") (pin "1") (pinfunction "1_1") (pintype "unspecified"))
      (node (ref "U1") (pin "7") (pinfunction "PF2-NRST_7") (pintype "unspecified"))
    )
    (net (code "10") (name "Net-(LED9-A)") (class "Default")
      (node (ref "LED9") (pin "2") (pinfunction "A_2") (pintype "unspecified"))
      (node (ref "R40") (pin "1") (pinfunction "1_1") (pintype "input"))
    )
    (net (code "11") (name "Net-(LED10-+)") (class "Default")
      (node (ref "LED10") (pin "1") (pinfunction "+_1") (pintype "unspecified"))
      (node (ref "R39") (pin "1") (pinfunction "1_1") (pintype "unspecified"))
    )
    (net (code "12") (name "Net-(LED11-A)") (class "Default")
      (node (ref "LED11") (pin "2") (pinfunction "A_2") (pintype "unspecified"))
      (node (ref "R38") (pin "1") (pinfunction "1_1") (pintype "unspecified"))
    )
    (net (code "13") (name "Net-(Q1-B)") (class "Default")
      (node (ref "Q1") (pin "1") (pinfunction "B_1") (pintype "unspecified"))
      (node (ref "R3") (pin "1") (pinfunction "1_1") (pintype "input"))
    )
    (net (code "14") (name "Net-(Q1-C)") (class "Default")
      (node (ref "Q1") (pin "3") (pinfunction "C_3") (pintype "unspecified"))
      (node (ref "R2") (pin "1") (pinfunction "1_1") (pintype "input"))
      (node (ref "U2") (pin "2") (pinfunction "RE#_2") (pintype "unspecified"))
      (node (ref "U2") (pin "3") (pinfunction "DE_3") (pintype "unspecified"))
    )
    (net (code "15") (name "Net-(U2-RO)") (class "Default")
      (node (ref "R1") (pin "2") (pinfunction "2_2") (pintype "unspecified"))
      (node (ref "U2") (pin "1") (pinfunction "RO_1") (pintype "unspecified"))
    )
    (net (code "16") (name "Net-(U3-BOOT)") (class "Default")
      (node (ref "C3") (pin "2") (pinfunction "2_2") (pintype "unspecified"))
      (node (ref "U3") (pin "6") (pinfunction "BOOT_6") (pintype "unspecified"))
    )
    (net (code "17") (name "Net-(U3-FB)") (class "Default")
      (node (ref "R6") (pin "1") (pinfunction "1_1") (pintype "unspecified"))
      (node (ref "R7") (pin "2") (pinfunction "2_2") (pintype "input"))
      (node (ref "U3") (pin "4") (pinfunction "FB_4") (pintype "unspecified"))
    )
    (net (code "18") (name "Net-(U3-SW)") (class "Default")
      (node (ref "C3") (pin "1") (pinfunction "1_1") (pintype "unspecified"))
      (node (ref "L1") (pin "1") (pinfunction "1_1") (pintype "unspecified"))
      (node (ref "U3") (pin "2") (pinfunction "SW_2") (pintype "unspecified"))
    )
    (net (code "19") (name "Net-(U4-SW)") (class "Default")
      (node (ref "C5") (pin "1") (pinfunction "1_1") (pintype "unspecified"))
      (node (ref "L2") (pin "1") (pinfunction "1_1") (pintype "unspecified"))
      (node (ref "U4") (pin "2") (pinfunction "SW_2") (pintype "unspecified"))
    )
    (net (code "20") (name "Net-(U4-VBST)") (class "Default")
      (node (ref "C5") (pin "2") (pinfunction "2_2") (pintype "unspecified"))
      (node (ref "U4") (pin "6") (pinfunction "VBST_6") (pintype "unspecified"))
    )
    (net (code "21") (name "Net-(U4-VFB)") (class "Default")
      (node (ref "R8") (pin "1") (pinfunction "1_1") (pintype "unspecified"))
      (node (ref "R9") (pin "2") (pinfunction "2_2") (pintype "unspecified"))
      (node (ref "U4") (pin "4") (pinfunction "VFB_4") (pintype "unspecified"))
    )
    (net (code "22") (name "Net-(U5-FB)") (class "Default")
      (node (ref "R11") (pin "1") (pinfunction "1_1") (pintype "unspecified"))
      (node (ref "R12") (pin "2") (pinfunction "2_2") (pintype "unspecified"))
      (node (ref "U5") (pin "1") (pinfunction "FB_1") (pintype "unspecified"))
    )
    (net (code "23") (name "Net-(U5-NC{slash}PG)") (class "Default")
      (node (ref "R10") (pin "2") (pinfunction "2_2") (pintype "unspecified"))
      (node (ref "U5") (pin "6") (pinfunction "NC/PG_6") (pintype "unspecified"))
    )
    (net (code "24") (name "Net-(U5-SW)") (class "Default")
      (node (ref "L3") (pin "1") (pinfunction "1_1") (pintype "unspecified"))
      (node (ref "U5") (pin "4") (pinfunction "SW_4") (pintype "unspecified"))
    )
    (net (code "25") (name "SWCLK") (class "Default")
      (node (ref "H7") (pin "2") (pinfunction "2_2") (pintype "unspecified"))
      (node (ref "U1") (pin "37") (pinfunction "PA14_37") (pintype "unspecified"))
    )
    (net (code "26") (name "SWDIO") (class "Default")
      (node (ref "H7") (pin "3") (pinfunction "3_3") (pintype "unspecified"))
      (node (ref "U1") (pin "34") (pinfunction "PA13_34") (pintype "unspecified"))
    )
    (net (code "27") (name "USART1_RX") (class "Default")
      (node (ref "CN5") (pin "2") (pinfunction "2_2") (pintype "unspecified"))
      (node (ref "U1") (pin "31") (pinfunction "PA10_31") (pintype "unspecified"))
    )
    (net (code "28") (name "USART1_TX") (class "Default")
      (node (ref "CN5") (pin "1") (pinfunction "1_1") (pintype "unspecified"))
      (node (ref "U1") (pin "30") (pinfunction "PA9_30") (pintype "unspecified"))
    )
    (net (code "29") (name "USART2_RX") (class "Default")
      (node (ref "R1") (pin "1") (pinfunction "1_1") (pintype "unspecified"))
      (node (ref "U1") (pin "13") (pinfunction "PA3_13") (pintype "unspecified"))
    )
    (net (code "30") (name "USART2_TX") (class "Default")
      (node (ref "R3") (pin "2") (pinfunction "2_2") (pintype "input"))
      (node (ref "U1") (pin "12") (pinfunction "PA2_12") (pintype "unspecified"))
    )
    (net (code "31") (name "XTAL1") (class "Default")
      (node (ref "C19") (pin "2") (pinfunction "2_2") (pintype "input"))
      (node (ref "U1") (pin "3") (pinfunction "PC14-OSC32_IN_3") (pintype "unspecified"))
      (node (ref "X1") (pin "1") (pinfunction "OSC1_1") (pintype "input"))
    )
    (net (code "32") (name "XTAL2") (class "Default")
      (node (ref "C18") (pin "2") (pinfunction "2_2") (pintype "input"))
      (node (ref "U1") (pin "4") (pinfunction "PC15-OSC32_OUT_4") (pintype "unspecified"))
      (node (ref "X1") (pin "2") (pinfunction "OSC2_2") (pintype "input"))
    )
    (net (code "33") (name "unconnected-(U1-PA0-Pad10)") (class "Default")
      (node (ref "U1") (pin "10") (pinfunction "PA0_10") (pintype "unspecified+no_connect"))
    )
    (net (code "34") (name "unconnected-(U1-PA1-Pad11)") (class "Default")
      (node (ref "U1") (pin "11") (pinfunction "PA1_11") (pintype "unspecified+no_connect"))
    )
    (net (code "35") (name "unconnected-(U1-PA4-Pad14)") (class "Default")
      (node (ref "U1") (pin "14") (pinfunction "PA4_14") (pintype "unspecified+no_connect"))
    )
    (net (code "36") (name "unconnected-(U1-PA5-Pad15)") (class "Default")
      (node (ref "U1") (pin "15") (pinfunction "PA5_15") (pintype "unspecified+no_connect"))
    )
    (net (code "37") (name "unconnected-(U1-PA6-Pad16)") (class "Default")
      (node (ref "U1") (pin "16") (pinfunction "PA6_16") (pintype "unspecified+no_connect"))
    )
    (net (code "38") (name "unconnected-(U1-PA7-Pad17)") (class "Default")
      (node (ref "U1") (pin "17") (pinfunction "PA7_17") (pintype "unspecified+no_connect"))
    )
    (net (code "39") (name "unconnected-(U1-PA8-Pad29)") (class "Default")
      (node (ref "U1") (pin "29") (pinfunction "PA8_29") (pintype "unspecified+no_connect"))
    )
    (net (code "40") (name "unconnected-(U1-PA11[PA9]-Pad32)") (class "Default")
      (node (ref "U1") (pin "32") (pinfunction "PA11[PA9]_32") (pintype "unspecified+no_connect"))
    )
    (net (code "41") (name "unconnected-(U1-PA12[PA10]-Pad33)") (class "Default")
      (node (ref "U1") (pin "33") (pinfunction "PA12[PA10]_33") (pintype "unspecified+no_connect"))
    )
    (net (code "42") (name "unconnected-(U1-PA15-Pad38)") (class "Default")
      (node (ref "U1") (pin "38") (pinfunction "PA15_38") (pintype "unspecified+no_connect"))
    )
    (net (code "43") (name "unconnected-(U1-PB0-Pad18)") (class "Default")
      (node (ref "U1") (pin "18") (pinfunction "PB0_18") (pintype "unspecified+no_connect"))
    )
    (net (code "44") (name "unconnected-(U1-PB1-Pad19)") (class "Default")
      (node (ref "U1") (pin "19") (pinfunction "PB1_19") (pintype "unspecified+no_connect"))
    )
    (net (code "45") (name "unconnected-(U1-PB2-Pad20)") (class "Default")
      (node (ref "U1") (pin "20") (pinfunction "PB2_20") (pintype "unspecified+no_connect"))
    )
    (net (code "46") (name "unconnected-(U1-PB3-Pad39)") (class "Default")
      (node (ref "U1") (pin "39") (pinfunction "PB3_39") (pintype "unspecified+no_connect"))
    )
    (net (code "47") (name "unconnected-(U1-PB4-Pad40)") (class "Default")
      (node (ref "U1") (pin "40") (pinfunction "PB4_40") (pintype "unspecified+no_connect"))
    )
    (net (code "48") (name "unconnected-(U1-PB5-Pad41)") (class "Default")
      (node (ref "U1") (pin "41") (pinfunction "PB5_41") (pintype "unspecified+no_connect"))
    )
    (net (code "49") (name "unconnected-(U1-PB6-Pad42)") (class "Default")
      (node (ref "U1") (pin "42") (pinfunction "PB6_42") (pintype "unspecified+no_connect"))
    )
    (net (code "50") (name "unconnected-(U1-PB7-Pad43)") (class "Default")
      (node (ref "U1") (pin "43") (pinfunction "PB7_43") (pintype "unspecified+no_connect"))
    )
    (net (code "51") (name "unconnected-(U1-PB8-Pad45)") (class "Default")
      (node (ref "U1") (pin "45") (pinfunction "PB8_45") (pintype "unspecified+no_connect"))
    )
    (net (code "52") (name "unconnected-(U1-PB9-Pad46)") (class "Default")
      (node (ref "U1") (pin "46") (pinfunction "PB9_46") (pintype "unspecified+no_connect"))
    )
    (net (code "53") (name "unconnected-(U1-PB10-Pad21)") (class "Default")
      (node (ref "U1") (pin "21") (pinfunction "PB10_21") (pintype "unspecified+no_connect"))
    )
    (net (code "54") (name "unconnected-(U1-PB11-Pad22)") (class "Default")
      (node (ref "U1") (pin "22") (pinfunction "PB11_22") (pintype "unspecified+no_connect"))
    )
    (net (code "55") (name "unconnected-(U1-PB12-Pad25)") (class "Default")
      (node (ref "U1") (pin "25") (pinfunction "PB12_25") (pintype "unspecified+no_connect"))
    )
    (net (code "56") (name "unconnected-(U1-PB13-Pad26)") (class "Default")
      (node (ref "U1") (pin "26") (pinfunction "PB13_26") (pintype "unspecified+no_connect"))
    )
    (net (code "57") (name "unconnected-(U1-PB14-Pad27)") (class "Default")
      (node (ref "U1") (pin "27") (pinfunction "PB14_27") (pintype "unspecified+no_connect"))
    )
    (net (code "58") (name "unconnected-(U1-PB15-Pad28)") (class "Default")
      (node (ref "U1") (pin "28") (pinfunction "PB15_28") (pintype "unspecified+no_connect"))
    )
    (net (code "59") (name "unconnected-(U1-PC13-Pad2)") (class "Default")
      (node (ref "U1") (pin "2") (pinfunction "PC13_2") (pintype "unspecified+no_connect"))
    )
    (net (code "60") (name "unconnected-(U1-PF0-OSC_IN-Pad5)") (class "Default")
      (node (ref "U1") (pin "5") (pinfunction "PF0-OSC_IN_5") (pintype "unspecified+no_connect"))
    )
    (net (code "61") (name "unconnected-(U1-PF1-OSC_OUT-Pad6)") (class "Default")
      (node (ref "U1") (pin "6") (pinfunction "PF1-OSC_OUT_6") (pintype "unspecified+no_connect"))
    )
    (net (code "62") (name "unconnected-(U1-VDDA{slash}VREF+-Pad9)") (class "Default")
      (node (ref "U1") (pin "9") (pinfunction "VDDA/VREF+_9") (pintype "unspecified+no_connect"))
    )
    (net (code "63") (name "unconnected-(U1-VSSA{slash}VREF--Pad8)") (class "Default")
      (node (ref "U1") (pin "8") (pinfunction "VSSA/VREF-_8") (pintype "unspecified+no_connect"))
    )
    (net (code "64") (name "unconnected-(U3-EN-Pad5)") (class "Default")
      (node (ref "U3") (pin "5") (pinfunction "EN_5") (pintype "unspecified+no_connect"))
    )
  )
)
